# main.net
KiCad netlist of a schematic drawn in Altium Designer
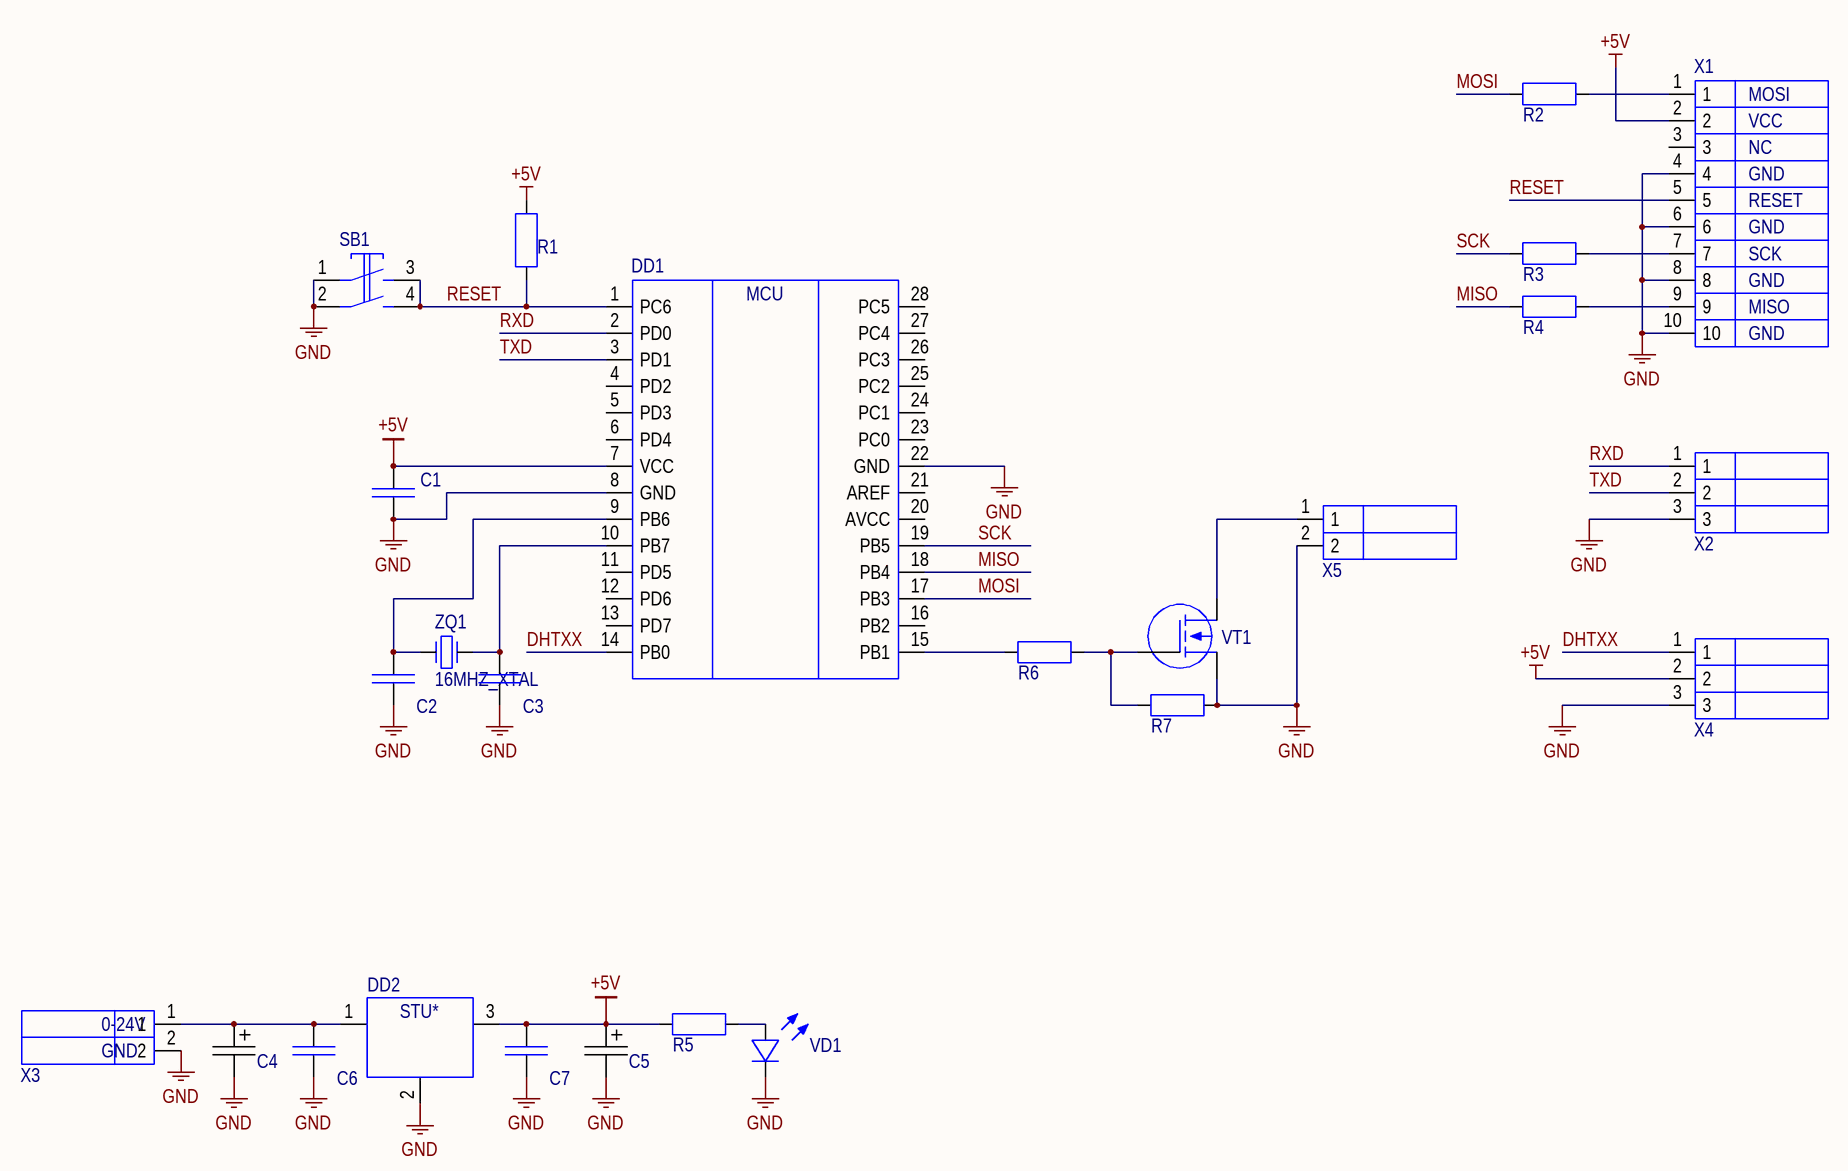
[diagram p0: main.SchDoc]

(export (version "E")
  (design (tool "Eeschema 10.0.6"))
  (components
    (comp (ref "C1")
      (value "100P50V_CAPRR")
      (footprint "CAPRR500W50L400T260H400")
      (description "CAP CER 100PF 50V C0G/NP0 RADIAL")
      (fields
        (field (name "MANUFACTURER") "Vishay BCcomponents")
        (field (name "MANUFACTURER PART NUMBER") "K101J10C0GF5UH5")
      )
      (libsource (lib "C") (part "100P50V_CAPRR"))
    )
    (comp (ref "C2")
      (value "30P50V_CAPRR")
      (footprint "CAPRR500W50L400T260H400")
      (description "CAP CER 30PF 50V C0G/NP0 RADIAL")
      (fields
        (field (name "MANUFACTURER") "Vishay BCcomponents")
        (field (name "MANUFACTURER PART NUMBER") "K300J10C0GF5UH5")
      )
      (libsource (lib "C") (part "30P50V_CAPRR"))
    )
    (comp (ref "C3")
      (value "30P50V_CAPRR")
      (footprint "CAPRR500W50L400T260H400")
      (description "CAP CER 30PF 50V C0G/NP0 RADIAL")
      (fields
        (field (name "MANUFACTURER") "Vishay BCcomponents")
        (field (name "MANUFACTURER PART NUMBER") "K300J10C0GF5UH5")
      )
      (libsource (lib "C") (part "30P50V_CAPRR"))
    )
    (comp (ref "C4")
      (value "100U16V_CAPAE")
      (footprint "CAPAE500X1100")
      (description "CAP ALUM 100UF 20% 16V RADIAL")
      (fields
        (field (name "MANUFACTURER") "Panasonic")
        (field (name "MANUFACTURER PART NUMBER") "ECA1CHG101")
      )
      (libsource (lib "C") (part "100U16V_CAPAE"))
    )
    (comp (ref "C5")
      (value "47U16V_CAPAE")
      (footprint "CAPAE500X1100")
      (description "CAP ALUM 47UF 20% 16V RADIAL")
      (fields
        (field (name "MANUFACTURER") "Panasonic")
        (field (name "MANUFACTURER PART NUMBER") "ECA1CHG470")
      )
      (libsource (lib "C") (part "47U16V_CAPAE"))
    )
    (comp (ref "C6")
      (value "100P50V_CAPRR")
      (footprint "CAPRR500W50L400T260H400")
      (description "CAP CER 100PF 50V C0G/NP0 RADIAL")
      (fields
        (field (name "MANUFACTURER") "Vishay BCcomponents")
        (field (name "MANUFACTURER PART NUMBER") "K101J10C0GF5UH5")
      )
      (libsource (lib "C") (part "100P50V_CAPRR"))
    )
    (comp (ref "C7")
      (value "100P50V_CAPRR")
      (footprint "CAPRR500W50L400T260H400")
      (description "CAP CER 100PF 50V C0G/NP0 RADIAL")
      (fields
        (field (name "MANUFACTURER") "Vishay BCcomponents")
        (field (name "MANUFACTURER PART NUMBER") "K101J10C0GF5UH5")
      )
      (libsource (lib "C") (part "100P50V_CAPRR"))
    )
    (comp (ref "DD1")
      (value "ATMEGA8")
      (footprint "PDIP28")
      (description "LORA RADIO 868MHZ")
      (fields
        (field (name "MANUFACTURER") "Microchip / Atmel")
        (field (name "MANUFACTURER PART NUMBER") "ATMEGA8-16PU")
      )
      (libsource (lib "IC") (part "ATMEGA8"))
    )
    (comp (ref "DD2")
      (value "L7805ABV")
      (footprint "TO-220")
      (description "IC REG LINEAR 5V 1.5A TO220AB")
      (fields (field (name "MANUFACTURER") "STMicroelectronics"))
      (libsource (lib "IC") (part "L7805"))
    )
    (comp (ref "R1")
      (value "CF14JT10K0")
      (footprint "RESAD800W55L600D230")
      (description "RES 10K OHM 1/4W 5% AXIAL")
      (fields (field (name "MANUFACTURER") "Stackpole Electronics"))
      (libsource (lib "R") (part "4.7K_AD800W55L600D230"))
    )
    (comp (ref "R2")
      (value "CF14JT220R0")
      (footprint "RESAD800W55L600D230")
      (description "RES 220 OHM 1/4W 5% AXIAL")
      (fields (field (name "MANUFACTURER") "Stackpole Electronics"))
      (libsource (lib "") (part "220R_AD800W55L600D230_1"))
    )
    (comp (ref "R3")
      (value "CF14JT220R0")
      (footprint "RESAD800W55L600D230")
      (description "RES 220 OHM 1/4W 5% AXIAL")
      (fields (field (name "MANUFACTURER") "Stackpole Electronics"))
      (libsource (lib "") (part "220R_AD800W55L600D230_1"))
    )
    (comp (ref "R4")
      (value "CF14JT220R0")
      (footprint "RESAD800W55L600D230")
      (description "RES 220 OHM 1/4W 5% AXIAL")
      (fields (field (name "MANUFACTURER") "Stackpole Electronics"))
      (libsource (lib "") (part "220R_AD800W55L600D230_1"))
    )
    (comp (ref "R5")
      (value "CF14JT220R0")
      (footprint "RESAD800W55L600D230")
      (description "RES 220 OHM 1/4W 5% AXIAL")
      (fields (field (name "MANUFACTURER") "Stackpole Electronics"))
      (libsource (lib "R") (part "220R_AD800W55L600D230"))
    )
    (comp (ref "R6")
      (value "CF14JT100R")
      (footprint "RESAD800W55L600D230")
      (description "RES 100 OHM 1/4W 5% AXIAL")
      (fields (field (name "MANUFACTURER") "Stackpole Electronics"))
      (libsource (lib "R") (part "100R_AD800W55L600D230"))
    )
    (comp (ref "R7")
      (value "CF14JT10K0")
      (footprint "RESAD800W55L600D230")
      (description "RES 10K OHM 1/4W 5% AXIAL")
      (fields (field (name "MANUFACTURER") "Stackpole Electronics"))
      (libsource (lib "R") (part "10K_AD800W55L600D230"))
    )
    (comp (ref "SB1")
      (value "BTN_TACTILE_6X6")
      (footprint "BTN_TACTILE_6X6")
      (description "SWITCH TACTILE SPST-NO 0.05A 24V")
      (fields
        (field (name "MANUFACTURER") "TE Connectivity Alcoswitch")
        (field (name "MANUFACTURER PART NUMBER") "1825910-6")
      )
      (libsource (lib "SW") (part "BTN_TACTILE_6X6"))
    )
    (comp (ref "VD1")
      (value "LED_SSL-LX5093GD-TR26")
      (footprint "LED500")
      (description "LED GREEN DIFFUSED T-1 3/4 T/H")
      (fields
        (field (name "MANUFACTURER") "Lumex")
        (field (name "MANUFACTURER PART NUMBER") "SSL-LX5093GD-TR26")
      )
      (libsource (lib "D") (part "LED_SSL-LX5093GD-TR26"))
    )
    (comp (ref "VT1")
      (value "IRF730")
      (footprint "TO-220-1")
      (description "MOSFET N-CH 400V 5.5A TO-220")
      (fields (field (name "MANUFACTURER") "STMicroelectronics"))
      (libsource (lib "VT") (part "IRF730"))
    )
    (comp (ref "X1")
      (value "ISP")
      (footprint "302_SERIES_10POS")
      (description "CONN HEADER VERT 10POS 2.54MM")
      (fields
        (field (name "MANUFACTURERPARTNUMBER") "302-S101")
        (field (name "MANUFACTURER") "On-Shore Technology")
      )
      (libsource (lib "X") (part "ISP"))
    )
    (comp (ref "X2")
      (value "61300311121")
      (footprint "PLS_3")
      (description "CONN HEADER VERT 8POS 2.54MM")
      (fields (field (name "MANUFACTURER") "Wurth Electronics"))
      (libsource (lib "X") (part "PLS_3"))
    )
    (comp (ref "X3")
      (value "PJ-037BH")
      (footprint "PJ-037BH")
      (description "CONN PWR JACK 2.5X5.5MM SOLDER")
      (fields (field (name "MANUFACTURER") "CUI"))
      (libsource (lib "X") (part "PJ-037BH"))
    )
    (comp (ref "X4")
      (value "61300311121")
      (footprint "PLS_3")
      (description "CONN HEADER VERT 8POS 2.54MM")
      (fields (field (name "MANUFACTURER") "Wurth Electronics"))
      (libsource (lib "X") (part "PLS_3"))
    )
    (comp (ref "X5") (value "SCREW3N2") (footprint "SCREW3N2") (libsource (lib "X") (part "SCREW3N2")))
    (comp (ref "ZQ1")
      (value "16MHZ_XTAL")
      (footprint "XTAL1050X465X350")
      (description "CRYSTAL 16.0000MHZ 20PF T/H")
      (fields
        (field (name "MANUFACTURER") "ECS International")
        (field (name "MANUFACTURER PART NUMBER") "ECS-160-20-4X")
      )
      (libsource (lib "XTAL") (part "16MHZ_XTAL"))
    )
  )
  (nets
    (net (code "1") (name "+5V") (class "Default")
      (node (ref "C1") (pin "2") (pinfunction "2_2") (pintype "passive"))
      (node (ref "C5") (pin "1") (pinfunction "1_1") (pintype "passive"))
      (node (ref "C7") (pin "2") (pinfunction "2_2") (pintype "passive"))
      (node (ref "DD1") (pin "7") (pinfunction "VCC_7") (pintype "passive"))
      (node (ref "DD2") (pin "3") (pinfunction "OUT_3") (pintype "passive"))
      (node (ref "R1") (pin "2") (pinfunction "2_2") (pintype "passive"))
      (node (ref "R5") (pin "2") (pinfunction "2_2") (pintype "passive"))
      (node (ref "X1") (pin "2") (pinfunction "2_2") (pintype "passive"))
      (node (ref "X4") (pin "2") (pinfunction "2_2") (pintype "passive"))
    )
    (net (code "2") (name "/DHTXX") (class "Default")
      (node (ref "DD1") (pin "14") (pinfunction "PB0_14") (pintype "passive"))
      (node (ref "X4") (pin "1") (pinfunction "1_1") (pintype "passive"))
    )
    (net (code "3") (name "/MISO") (class "Default")
      (node (ref "DD1") (pin "18") (pinfunction "PB4_18") (pintype "passive"))
      (node (ref "R4") (pin "1") (pinfunction "1_1") (pintype "passive"))
    )
    (net (code "4") (name "/MOSI") (class "Default")
      (node (ref "DD1") (pin "17") (pinfunction "PB3_17") (pintype "passive"))
      (node (ref "R2") (pin "1") (pinfunction "1_1") (pintype "passive"))
    )
    (net (code "5") (name "/RESET") (class "Default")
      (node (ref "DD1") (pin "1") (pinfunction "PC6_1") (pintype "passive"))
      (node (ref "R1") (pin "1") (pinfunction "1_1") (pintype "passive"))
      (node (ref "SB1") (pin "3") (pinfunction "3_3") (pintype "passive"))
      (node (ref "SB1") (pin "4") (pinfunction "4_4") (pintype "passive"))
      (node (ref "X1") (pin "5") (pinfunction "5_5") (pintype "passive"))
    )
    (net (code "6") (name "/RXD") (class "Default")
      (node (ref "DD1") (pin "2") (pinfunction "PD0_2") (pintype "passive"))
      (node (ref "X2") (pin "1") (pinfunction "1_1") (pintype "passive"))
    )
    (net (code "7") (name "/SCK") (class "Default")
      (node (ref "DD1") (pin "19") (pinfunction "PB5_19") (pintype "passive"))
      (node (ref "R3") (pin "1") (pinfunction "1_1") (pintype "passive"))
    )
    (net (code "8") (name "/TXD") (class "Default")
      (node (ref "DD1") (pin "3") (pinfunction "PD1_3") (pintype "passive"))
      (node (ref "X2") (pin "2") (pinfunction "2_2") (pintype "passive"))
    )
    (net (code "9") (name "GND") (class "Default")
      (node (ref "C1") (pin "1") (pinfunction "1_1") (pintype "passive"))
      (node (ref "C2") (pin "1") (pinfunction "1_1") (pintype "passive"))
      (node (ref "C3") (pin "1") (pinfunction "1_1") (pintype "passive"))
      (node (ref "C4") (pin "2") (pinfunction "2_2") (pintype "passive"))
      (node (ref "C5") (pin "2") (pinfunction "2_2") (pintype "passive"))
      (node (ref "C6") (pin "1") (pinfunction "1_1") (pintype "passive"))
      (node (ref "C7") (pin "1") (pinfunction "1_1") (pintype "passive"))
      (node (ref "DD1") (pin "22") (pinfunction "GND_22") (pintype "passive"))
      (node (ref "DD1") (pin "8") (pinfunction "GND_8") (pintype "passive"))
      (node (ref "DD2") (pin "2") (pinfunction "GND_2") (pintype "passive"))
      (node (ref "R7") (pin "2") (pinfunction "2_2") (pintype "passive"))
      (node (ref "SB1") (pin "1") (pinfunction "1_1") (pintype "passive"))
      (node (ref "SB1") (pin "2") (pinfunction "2_2") (pintype "passive"))
      (node (ref "VD1") (pin "K") (pinfunction "K_K") (pintype "passive"))
      (node (ref "VT1") (pin "3") (pinfunction "3_3") (pintype "passive"))
      (node (ref "X1") (pin "10") (pinfunction "10_10") (pintype "passive"))
      (node (ref "X1") (pin "4") (pinfunction "4_4") (pintype "passive"))
      (node (ref "X1") (pin "6") (pinfunction "6_6") (pintype "passive"))
      (node (ref "X1") (pin "8") (pinfunction "8_8") (pintype "passive"))
      (node (ref "X2") (pin "3") (pinfunction "3_3") (pintype "passive"))
      (node (ref "X3") (pin "2") (pinfunction "2_2") (pintype "passive"))
      (node (ref "X4") (pin "3") (pinfunction "3_3") (pintype "passive"))
      (node (ref "X5") (pin "2") (pinfunction "2_2") (pintype "passive"))
    )
    (net (code "10") (name "Net-(DD1-PB1)") (class "Default")
      (node (ref "DD1") (pin "15") (pinfunction "PB1_15") (pintype "passive"))
      (node (ref "R6") (pin "1") (pinfunction "1_1") (pintype "passive"))
    )
    (net (code "11") (name "Net-(DD1-PB6)") (class "Default")
      (node (ref "C2") (pin "2") (pinfunction "2_2") (pintype "passive"))
      (node (ref "DD1") (pin "9") (pinfunction "PB6_9") (pintype "passive"))
      (node (ref "ZQ1") (pin "2") (pinfunction "2_2") (pintype "passive"))
    )
    (net (code "12") (name "Net-(DD1-PB7)") (class "Default")
      (node (ref "C3") (pin "2") (pinfunction "2_2") (pintype "passive"))
      (node (ref "DD1") (pin "10") (pinfunction "PB7_10") (pintype "passive"))
      (node (ref "ZQ1") (pin "1") (pinfunction "1_1") (pintype "passive"))
    )
    (net (code "13") (name "Net-(DD2-IN)") (class "Default")
      (node (ref "C4") (pin "1") (pinfunction "1_1") (pintype "passive"))
      (node (ref "C6") (pin "2") (pinfunction "2_2") (pintype "passive"))
      (node (ref "DD2") (pin "1") (pinfunction "IN_1") (pintype "passive"))
      (node (ref "X3") (pin "1") (pinfunction "1_1") (pintype "passive"))
    )
    (net (code "14") (name "Net-(R2-Pad2)") (class "Default")
      (node (ref "R2") (pin "2") (pinfunction "2_2") (pintype "passive"))
      (node (ref "X1") (pin "1") (pinfunction "1_1") (pintype "passive"))
    )
    (net (code "15") (name "Net-(R3-Pad2)") (class "Default")
      (node (ref "R3") (pin "2") (pinfunction "2_2") (pintype "passive"))
      (node (ref "X1") (pin "7") (pinfunction "7_7") (pintype "passive"))
    )
    (net (code "16") (name "Net-(R4-Pad2)") (class "Default")
      (node (ref "R4") (pin "2") (pinfunction "2_2") (pintype "passive"))
      (node (ref "X1") (pin "9") (pinfunction "9_9") (pintype "passive"))
    )
    (net (code "17") (name "Net-(R5-Pad1)") (class "Default")
      (node (ref "R5") (pin "1") (pinfunction "1_1") (pintype "passive"))
      (node (ref "VD1") (pin "A") (pinfunction "A_A") (pintype "passive"))
    )
    (net (code "18") (name "Net-(R6-Pad2)") (class "Default")
      (node (ref "R6") (pin "2") (pinfunction "2_2") (pintype "passive"))
      (node (ref "R7") (pin "1") (pinfunction "1_1") (pintype "passive"))
      (node (ref "VT1") (pin "1") (pinfunction "1_1") (pintype "passive"))
    )
    (net (code "19") (name "Net-(VT1-Pad2)") (class "Default")
      (node (ref "VT1") (pin "2") (pinfunction "2_2") (pintype "passive"))
      (node (ref "X5") (pin "1") (pinfunction "1_1") (pintype "passive"))
    )
    (net (code "20") (name "unconnected-(DD1-AREF-Pad21)") (class "Default")
      (node (ref "DD1") (pin "21") (pinfunction "AREF_21") (pintype "passive"))
    )
    (net (code "21") (name "unconnected-(DD1-AVCC-Pad20)") (class "Default")
      (node (ref "DD1") (pin "20") (pinfunction "AVCC_20") (pintype "passive"))
    )
    (net (code "22") (name "unconnected-(DD1-PB2-Pad16)") (class "Default")
      (node (ref "DD1") (pin "16") (pinfunction "PB2_16") (pintype "passive"))
    )
    (net (code "23") (name "unconnected-(DD1-PC0-Pad23)") (class "Default")
      (node (ref "DD1") (pin "23") (pinfunction "PC0_23") (pintype "passive"))
    )
    (net (code "24") (name "unconnected-(DD1-PC1-Pad24)") (class "Default")
      (node (ref "DD1") (pin "24") (pinfunction "PC1_24") (pintype "passive"))
    )
    (net (code "25") (name "unconnected-(DD1-PC2-Pad25)") (class "Default")
      (node (ref "DD1") (pin "25") (pinfunction "PC2_25") (pintype "passive"))
    )
    (net (code "26") (name "unconnected-(DD1-PC3-Pad26)") (class "Default")
      (node (ref "DD1") (pin "26") (pinfunction "PC3_26") (pintype "passive"))
    )
    (net (code "27") (name "unconnected-(DD1-PC4-Pad27)") (class "Default")
      (node (ref "DD1") (pin "27") (pinfunction "PC4_27") (pintype "passive"))
    )
    (net (code "28") (name "unconnected-(DD1-PC5-Pad28)") (class "Default")
      (node (ref "DD1") (pin "28") (pinfunction "PC5_28") (pintype "passive"))
    )
    (net (code "29") (name "unconnected-(DD1-PD2-Pad4)") (class "Default")
      (node (ref "DD1") (pin "4") (pinfunction "PD2_4") (pintype "passive"))
    )
    (net (code "30") (name "unconnected-(DD1-PD3-Pad5)") (class "Default")
      (node (ref "DD1") (pin "5") (pinfunction "PD3_5") (pintype "passive"))
    )
    (net (code "31") (name "unconnected-(DD1-PD4-Pad6)") (class "Default")
      (node (ref "DD1") (pin "6") (pinfunction "PD4_6") (pintype "passive"))
    )
    (net (code "32") (name "unconnected-(DD1-PD5-Pad11)") (class "Default")
      (node (ref "DD1") (pin "11") (pinfunction "PD5_11") (pintype "passive"))
    )
    (net (code "33") (name "unconnected-(DD1-PD6-Pad12)") (class "Default")
      (node (ref "DD1") (pin "12") (pinfunction "PD6_12") (pintype "passive"))
    )
    (net (code "34") (name "unconnected-(DD1-PD7-Pad13)") (class "Default")
      (node (ref "DD1") (pin "13") (pinfunction "PD7_13") (pintype "passive"))
    )
    (net (code "35") (name "unconnected-(X1-Pad3)") (class "Default")
      (node (ref "X1") (pin "3") (pinfunction "3_3") (pintype "passive"))
    )
  )
)
